# schematic.net
KiCad netlist of a schematic drawn in EAGLE
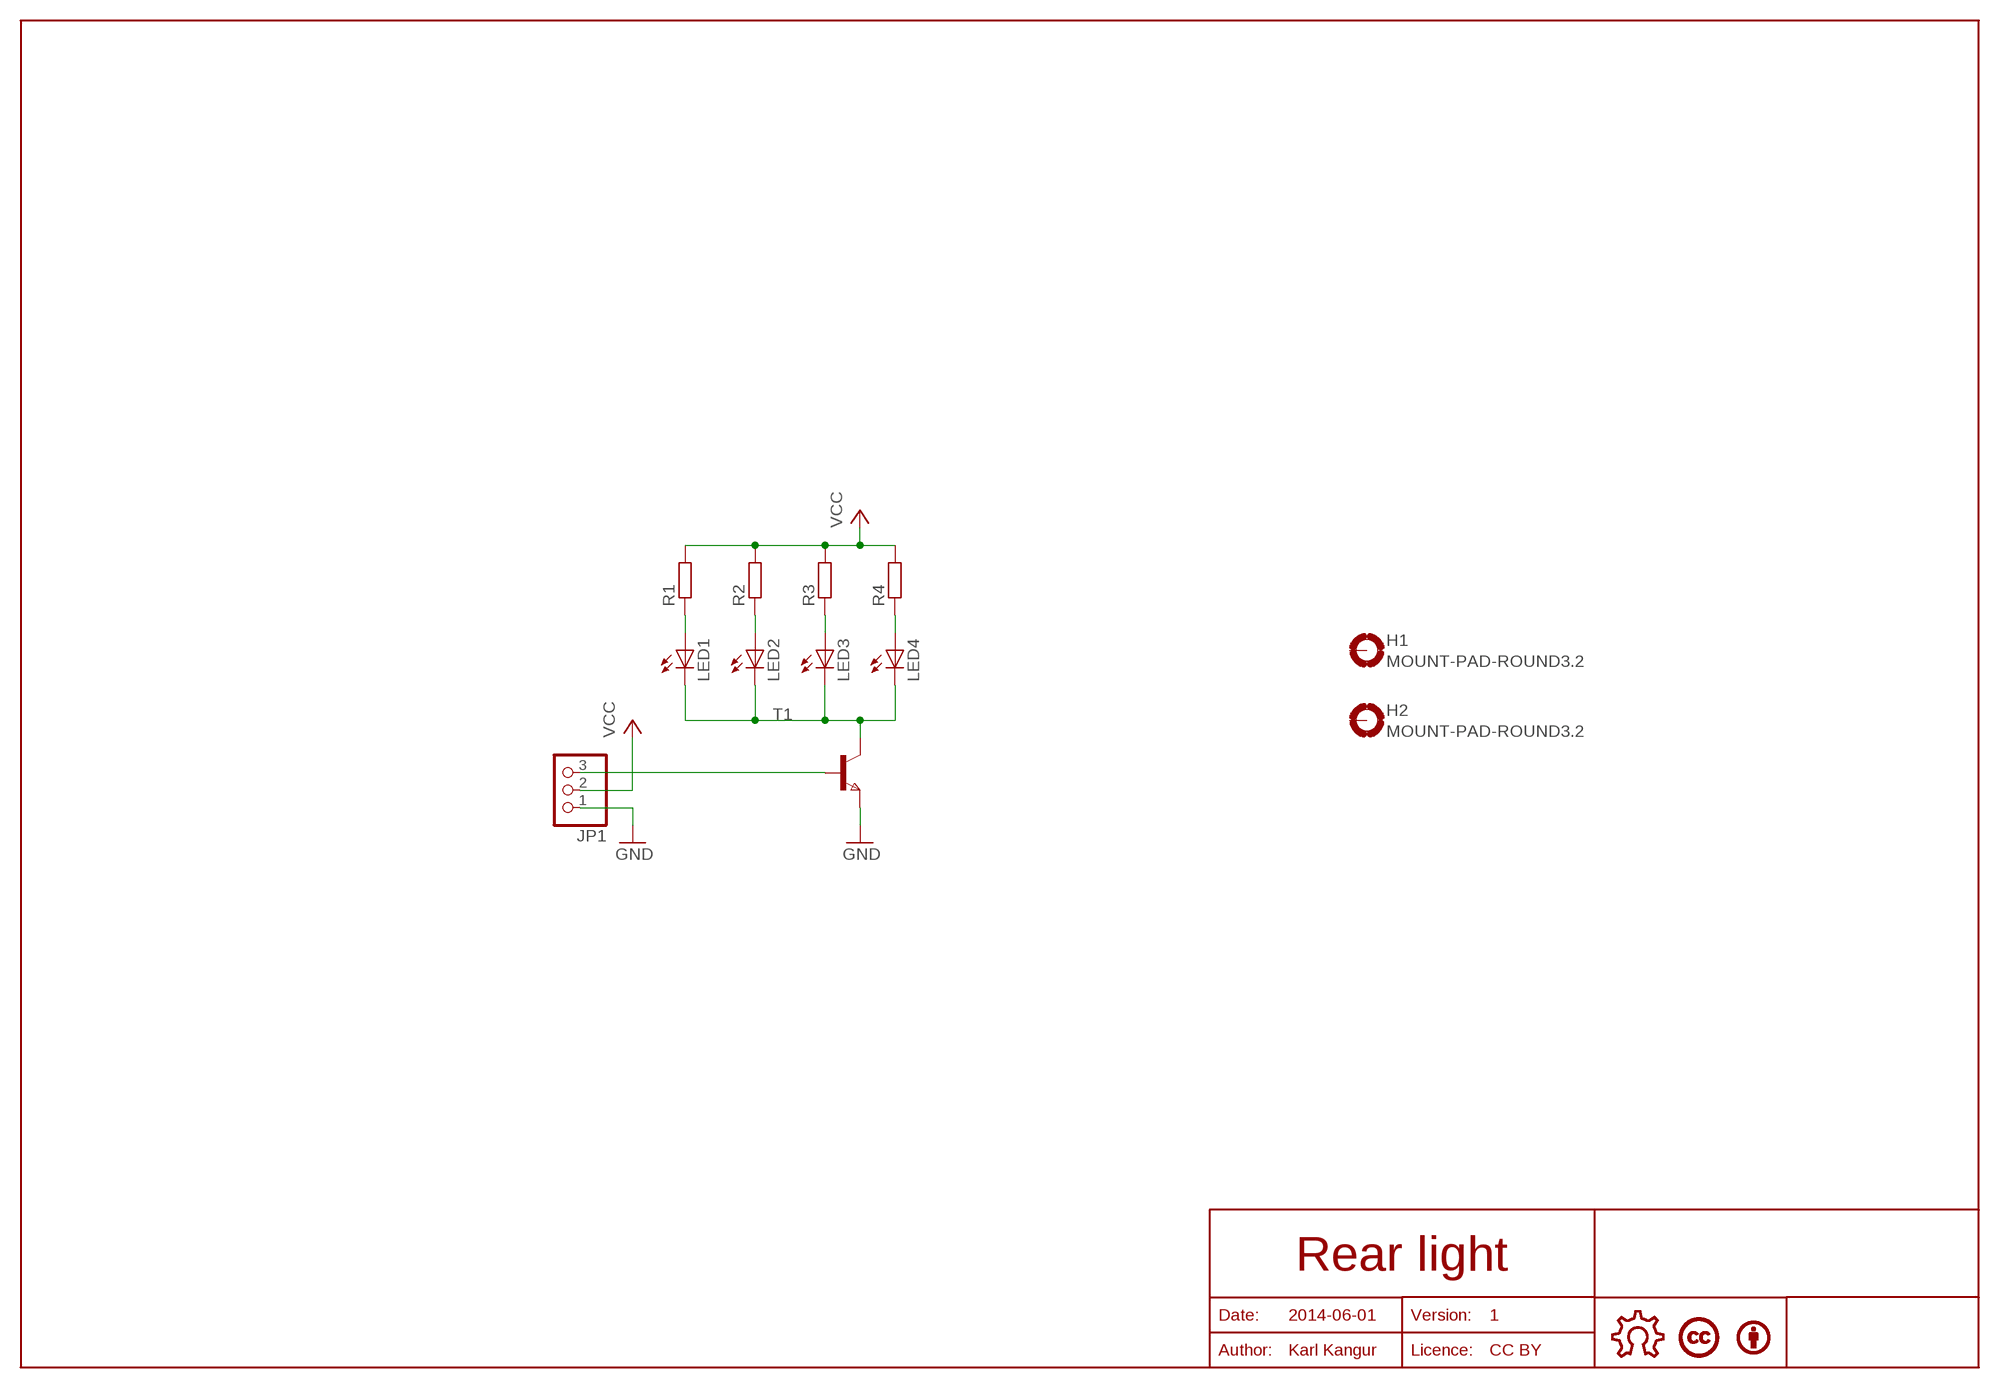
[diagram p0: schematic, sheet 1]

(export (version "E")
  (design (tool "Eeschema 10.0.6"))
  (components
    (comp (ref "BY1")
      (value "BYBOTTOM")
      (footprint "eagle-import:BY")
      (libsource (lib "eagle-import") (part "BYBOTTOM"))
    )
    (comp (ref "H1")
      (value "MOUNT-PAD-ROUND3.2")
      (footprint "eagle-import:3,2-PAD")
      (libsource (lib "eagle-import") (part "MOUNT-PAD-ROUND3.2"))
    )
    (comp (ref "H2")
      (value "MOUNT-PAD-ROUND3.2")
      (footprint "eagle-import:3,2-PAD")
      (libsource (lib "eagle-import") (part "MOUNT-PAD-ROUND3.2"))
    )
    (comp (ref "JP1")
      (value "PINHD-1X3")
      (footprint "eagle-import:1X03")
      (libsource (lib "eagle-import") (part "PINHD-1X3"))
    )
    (comp (ref "LED1")
      (value "LED3MM")
      (footprint "eagle-import:LED3MM")
      (libsource (lib "eagle-import") (part "LED3MM"))
    )
    (comp (ref "LED2")
      (value "LED3MM")
      (footprint "eagle-import:LED3MM")
      (libsource (lib "eagle-import") (part "LED3MM"))
    )
    (comp (ref "LED3")
      (value "LED3MM")
      (footprint "eagle-import:LED3MM")
      (libsource (lib "eagle-import") (part "LED3MM"))
    )
    (comp (ref "LED4")
      (value "LED3MM")
      (footprint "eagle-import:LED3MM")
      (libsource (lib "eagle-import") (part "LED3MM"))
    )
    (comp (ref "LICENCE1")
      (value "LICENCECC-BOTTOM")
      (footprint "eagle-import:CREATIVE-COMMONS")
      (libsource (lib "eagle-import") (part "LICENCECC-BOTTOM"))
    )
    (comp (ref "R1")
      (value "R-EU_R0805")
      (footprint "eagle-import:R0805")
      (libsource (lib "eagle-import") (part "R-EU_R0805"))
    )
    (comp (ref "R2")
      (value "R-EU_R0805")
      (footprint "eagle-import:R0805")
      (libsource (lib "eagle-import") (part "R-EU_R0805"))
    )
    (comp (ref "R3")
      (value "R-EU_R0805")
      (footprint "eagle-import:R0805")
      (libsource (lib "eagle-import") (part "R-EU_R0805"))
    )
    (comp (ref "R4")
      (value "R-EU_R0805")
      (footprint "eagle-import:R0805")
      (libsource (lib "eagle-import") (part "R-EU_R0805"))
    )
    (comp (ref "T1")
      (value "NPNSOT323")
      (footprint "eagle-import:SOT323")
      (fields (field (name "MPN") "DSS4160U-7"))
      (libsource (lib "eagle-import") (part "NPNSOT323"))
    )
    (comp (ref "U$10")
      (value "OPEN-HARDWARE-LOGOBOTTOM-SMALL")
      (footprint "eagle-import:OPEN-HARDWARE-BOTTOM-SMALL")
      (libsource (lib "eagle-import") (part "OPEN-HARDWARE-LOGOBOTTOM-SMALL"))
    )
  )
  (nets
    (net (code "1") (name "GND") (class "Default")
      (node (ref "JP1") (pin "1") (pinfunction "1_1") (pintype "passive"))
      (node (ref "T1") (pin "3") (pinfunction "E_3") (pintype "passive"))
    )
    (net (code "2") (name "Net-(LED1-C)") (class "Default")
      (node (ref "LED1") (pin "K") (pinfunction "C_K") (pintype "passive"))
      (node (ref "LED2") (pin "K") (pinfunction "C_K") (pintype "passive"))
      (node (ref "LED3") (pin "K") (pinfunction "C_K") (pintype "passive"))
      (node (ref "LED4") (pin "K") (pinfunction "C_K") (pintype "passive"))
      (node (ref "T1") (pin "1") (pinfunction "C_1") (pintype "passive"))
    )
    (net (code "3") (name "Net-(LED1-PadA)") (class "Default")
      (node (ref "LED1") (pin "A") (pinfunction "A_A") (pintype "passive"))
      (node (ref "R1") (pin "1") (pinfunction "1_1") (pintype "passive"))
    )
    (net (code "4") (name "Net-(LED2-PadA)") (class "Default")
      (node (ref "LED2") (pin "A") (pinfunction "A_A") (pintype "passive"))
      (node (ref "R2") (pin "1") (pinfunction "1_1") (pintype "passive"))
    )
    (net (code "5") (name "Net-(LED3-PadA)") (class "Default")
      (node (ref "LED3") (pin "A") (pinfunction "A_A") (pintype "passive"))
      (node (ref "R3") (pin "1") (pinfunction "1_1") (pintype "passive"))
    )
    (net (code "6") (name "Net-(LED4-PadA)") (class "Default")
      (node (ref "LED4") (pin "A") (pinfunction "A_A") (pintype "passive"))
      (node (ref "R4") (pin "1") (pinfunction "1_1") (pintype "passive"))
    )
    (net (code "7") (name "Net-(T1-B)") (class "Default")
      (node (ref "JP1") (pin "3") (pinfunction "3_3") (pintype "passive"))
      (node (ref "T1") (pin "2") (pinfunction "B_2") (pintype "passive"))
    )
    (net (code "8") (name "VCC") (class "Default")
      (node (ref "JP1") (pin "2") (pinfunction "2_2") (pintype "passive"))
      (node (ref "R1") (pin "2") (pinfunction "2_2") (pintype "passive"))
      (node (ref "R2") (pin "2") (pinfunction "2_2") (pintype "passive"))
      (node (ref "R3") (pin "2") (pinfunction "2_2") (pintype "passive"))
      (node (ref "R4") (pin "2") (pinfunction "2_2") (pintype "passive"))
    )
    (net (code "9") (name "unconnected-(H1-MOUNT-PadB3,2)") (class "Default")
      (node (ref "H1") (pin "B3,2") (pinfunction "MOUNT_B3,2") (pintype "passive"))
    )
    (net (code "10") (name "unconnected-(H2-MOUNT-PadB3,2)") (class "Default")
      (node (ref "H2") (pin "B3,2") (pinfunction "MOUNT_B3,2") (pintype "passive"))
    )
  )
)
